# motor_driver.net
KiCad netlist of a schematic drawn in EAGLE
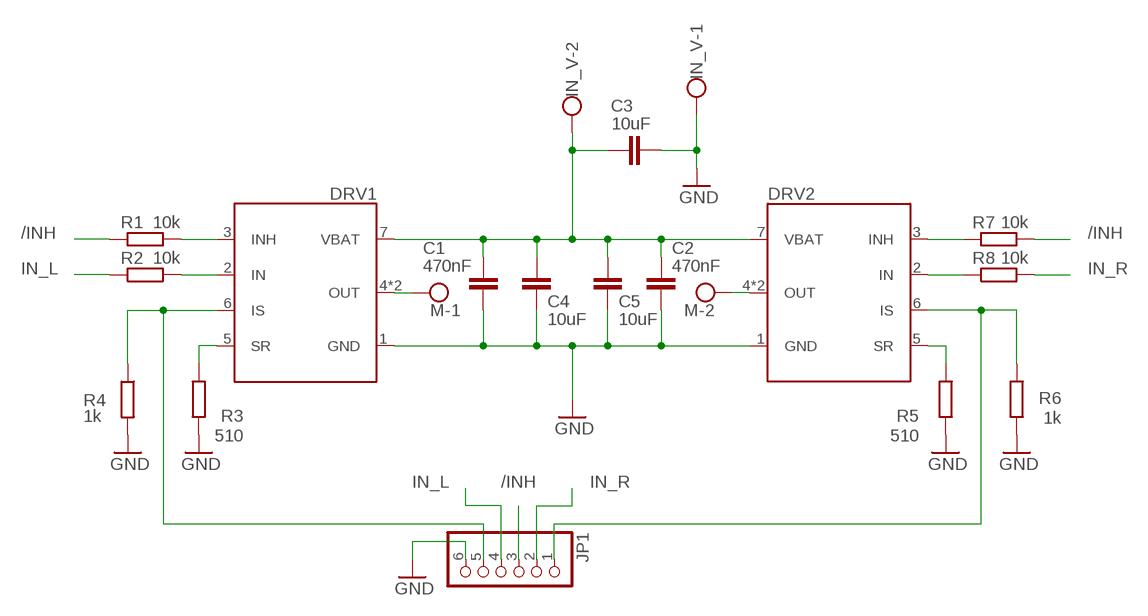
[diagram p0: schematic, sheet 1]

(export (version "E")
  (design (tool "Eeschema 10.0.6"))
  (components
    (comp (ref "C1")
      (value "470nF")
      (footprint "eagle-import:C0805")
      (libsource (lib "eagle-import") (part "C-EUC0805"))
    )
    (comp (ref "C2")
      (value "470nF")
      (footprint "eagle-import:C0805")
      (libsource (lib "eagle-import") (part "C-EUC0805"))
    )
    (comp (ref "C3")
      (value "10uF")
      (footprint "eagle-import:C1206")
      (libsource (lib "eagle-import") (part "resistor_C-EUC1206"))
    )
    (comp (ref "C4")
      (value "10uF")
      (footprint "eagle-import:C1206")
      (libsource (lib "eagle-import") (part "resistor_C-EUC1206"))
    )
    (comp (ref "C5")
      (value "10uF")
      (footprint "eagle-import:C1206")
      (libsource (lib "eagle-import") (part "resistor_C-EUC1206"))
    )
    (comp (ref "DRV1")
      (value "FAN7093_F085SMD")
      (footprint "eagle-import:TO-263-8")
      (libsource (lib "eagle-import") (part "FAN7093_F085SMD"))
    )
    (comp (ref "DRV2")
      (value "FAN7093_F085SMD")
      (footprint "eagle-import:TO-263-8")
      (libsource (lib "eagle-import") (part "FAN7093_F085SMD"))
    )
    (comp (ref "IN_V")
      (value "W237-102")
      (footprint "eagle-import:W237-102")
      (fields (field (name "MPN") "237-102"))
      (libsource (lib "eagle-import") (part "W237-102"))
    )
    (comp (ref "JP1")
      (value "PINHD-1X6")
      (footprint "eagle-import:1X06")
      (libsource (lib "eagle-import") (part "PINHD-1X6"))
    )
    (comp (ref "M")
      (value "W237-102")
      (footprint "eagle-import:W237-102")
      (fields (field (name "MPN") "237-102"))
      (libsource (lib "eagle-import") (part "W237-102"))
    )
    (comp (ref "R1")
      (value "10k")
      (footprint "eagle-import:R0805")
      (libsource (lib "eagle-import") (part "R-EU_R0805"))
    )
    (comp (ref "R2")
      (value "10k")
      (footprint "eagle-import:R0805")
      (libsource (lib "eagle-import") (part "R-EU_R0805"))
    )
    (comp (ref "R3")
      (value "510")
      (footprint "eagle-import:R0805")
      (libsource (lib "eagle-import") (part "R-EU_R0805"))
    )
    (comp (ref "R4")
      (value "1k")
      (footprint "eagle-import:R0805")
      (libsource (lib "eagle-import") (part "R-EU_R0805"))
    )
    (comp (ref "R5")
      (value "510")
      (footprint "eagle-import:R0805")
      (libsource (lib "eagle-import") (part "R-EU_R0805"))
    )
    (comp (ref "R6")
      (value "1k")
      (footprint "eagle-import:R0805")
      (libsource (lib "eagle-import") (part "R-EU_R0805"))
    )
    (comp (ref "R7")
      (value "10k")
      (footprint "eagle-import:R0805")
      (libsource (lib "eagle-import") (part "R-EU_R0805"))
    )
    (comp (ref "R8")
      (value "10k")
      (footprint "eagle-import:R0805")
      (libsource (lib "eagle-import") (part "R-EU_R0805"))
    )
  )
  (nets
    (net (code "1") (name "/IN_L") (class "Default")
      (node (ref "JP1") (pin "4") (pinfunction "4_4") (pintype "passive"))
      (node (ref "R2") (pin "1") (pinfunction "1_1") (pintype "passive"))
    )
    (net (code "2") (name "/IN_R") (class "Default")
      (node (ref "JP1") (pin "2") (pinfunction "2_2") (pintype "passive"))
      (node (ref "R8") (pin "2") (pinfunction "2_2") (pintype "passive"))
    )
    (net (code "3") (name "/{slash}INH") (class "Default")
      (node (ref "JP1") (pin "3") (pinfunction "3_3") (pintype "passive"))
      (node (ref "R1") (pin "1") (pinfunction "1_1") (pintype "passive"))
      (node (ref "R7") (pin "2") (pinfunction "2_2") (pintype "passive"))
    )
    (net (code "4") (name "GND") (class "Default")
      (node (ref "C1") (pin "2") (pinfunction "2_2") (pintype "passive"))
      (node (ref "C2") (pin "2") (pinfunction "2_2") (pintype "passive"))
      (node (ref "C3") (pin "2") (pinfunction "2_2") (pintype "passive"))
      (node (ref "C4") (pin "2") (pinfunction "2_2") (pintype "passive"))
      (node (ref "C5") (pin "2") (pinfunction "2_2") (pintype "passive"))
      (node (ref "DRV1") (pin "1") (pinfunction "GND_1") (pintype "bidirectional"))
      (node (ref "DRV2") (pin "1") (pinfunction "GND_1") (pintype "bidirectional"))
      (node (ref "IN_V") (pin "1") (pinfunction "KL_1") (pintype "passive"))
      (node (ref "JP1") (pin "6") (pinfunction "6_6") (pintype "passive"))
      (node (ref "R3") (pin "1") (pinfunction "1_1") (pintype "passive"))
      (node (ref "R4") (pin "2") (pinfunction "2_2") (pintype "passive"))
      (node (ref "R5") (pin "1") (pinfunction "1_1") (pintype "passive"))
      (node (ref "R6") (pin "1") (pinfunction "1_1") (pintype "passive"))
    )
    (net (code "5") (name "Net-(DRV1-IN)") (class "Default")
      (node (ref "DRV1") (pin "2") (pinfunction "IN_2") (pintype "bidirectional"))
      (node (ref "R2") (pin "2") (pinfunction "2_2") (pintype "passive"))
    )
    (net (code "6") (name "Net-(DRV1-INH)") (class "Default")
      (node (ref "DRV1") (pin "3") (pinfunction "INH_3") (pintype "bidirectional"))
      (node (ref "R1") (pin "2") (pinfunction "2_2") (pintype "passive"))
    )
    (net (code "7") (name "Net-(DRV1-IS)") (class "Default")
      (node (ref "DRV1") (pin "6") (pinfunction "IS_6") (pintype "bidirectional"))
      (node (ref "JP1") (pin "5") (pinfunction "5_5") (pintype "passive"))
      (node (ref "R4") (pin "1") (pinfunction "1_1") (pintype "passive"))
    )
    (net (code "8") (name "Net-(DRV1-SR)") (class "Default")
      (node (ref "DRV1") (pin "5") (pinfunction "SR_5") (pintype "bidirectional"))
      (node (ref "R3") (pin "2") (pinfunction "2_2") (pintype "passive"))
    )
    (net (code "9") (name "Net-(DRV1-VBAT)") (class "Default")
      (node (ref "C1") (pin "1") (pinfunction "1_1") (pintype "passive"))
      (node (ref "C2") (pin "1") (pinfunction "1_1") (pintype "passive"))
      (node (ref "C3") (pin "1") (pinfunction "1_1") (pintype "passive"))
      (node (ref "C4") (pin "1") (pinfunction "1_1") (pintype "passive"))
      (node (ref "C5") (pin "1") (pinfunction "1_1") (pintype "passive"))
      (node (ref "DRV1") (pin "7") (pinfunction "VBAT_7") (pintype "bidirectional"))
      (node (ref "DRV2") (pin "7") (pinfunction "VBAT_7") (pintype "bidirectional"))
      (node (ref "IN_V") (pin "2") (pinfunction "KL_2") (pintype "passive"))
    )
    (net (code "10") (name "Net-(DRV2-IN)") (class "Default")
      (node (ref "DRV2") (pin "2") (pinfunction "IN_2") (pintype "bidirectional"))
      (node (ref "R8") (pin "1") (pinfunction "1_1") (pintype "passive"))
    )
    (net (code "11") (name "Net-(DRV2-INH)") (class "Default")
      (node (ref "DRV2") (pin "3") (pinfunction "INH_3") (pintype "bidirectional"))
      (node (ref "R7") (pin "1") (pinfunction "1_1") (pintype "passive"))
    )
    (net (code "12") (name "Net-(DRV2-IS)") (class "Default")
      (node (ref "DRV2") (pin "6") (pinfunction "IS_6") (pintype "bidirectional"))
      (node (ref "JP1") (pin "1") (pinfunction "1_1") (pintype "passive"))
      (node (ref "R6") (pin "2") (pinfunction "2_2") (pintype "passive"))
    )
    (net (code "13") (name "Net-(DRV2-SR)") (class "Default")
      (node (ref "DRV2") (pin "5") (pinfunction "SR_5") (pintype "bidirectional"))
      (node (ref "R5") (pin "2") (pinfunction "2_2") (pintype "passive"))
    )
    (net (code "14") (name "Net-(MA-KL)") (class "Default")
      (node (ref "DRV1") (pin "4") (pinfunction "OUT_4") (pintype "bidirectional"))
      (node (ref "DRV1") (pin "8") (pinfunction "OUT_8") (pintype "bidirectional"))
      (node (ref "M") (pin "1") (pinfunction "KL_1") (pintype "passive"))
    )
    (net (code "15") (name "Net-(MB-KL)") (class "Default")
      (node (ref "DRV2") (pin "4") (pinfunction "OUT_4") (pintype "bidirectional"))
      (node (ref "DRV2") (pin "8") (pinfunction "OUT_8") (pintype "bidirectional"))
      (node (ref "M") (pin "2") (pinfunction "KL_2") (pintype "passive"))
    )
  )
)
